# YOTSUBA_AP_EM_ver_1_0.net
KiCad netlist of a schematic drawn in EAGLE
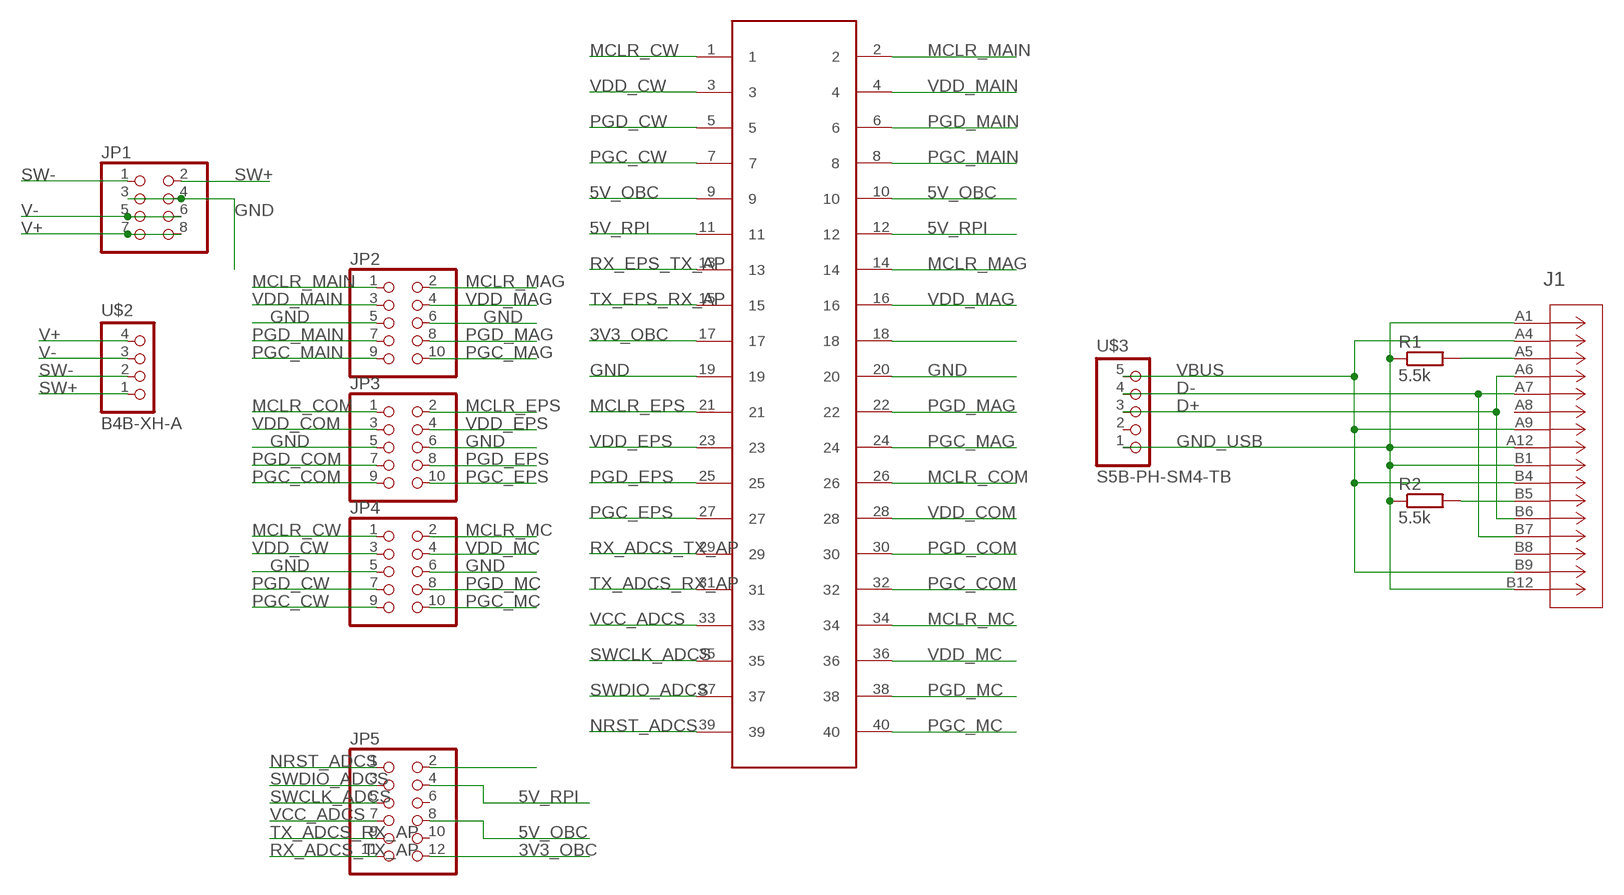
[diagram p0: schematic, sheet 1]

(export (version "E")
  (design (tool "Eeschema 10.0.6"))
  (components
    (comp (ref "J1")
      (value "217182-0001")
      (footprint "eagle-import:CONN_217182-0001_MOL")
      (fields (field (name "COPYRIGHT") "Copyright (C) 2022 Ultra Librarian. All rights reserved."))
      (libsource (lib "eagle-import") (part "217182-0001"))
    )
    (comp (ref "JP1")
      (value "PINHD-2X4")
      (footprint "eagle-import:2X04")
      (libsource (lib "eagle-import") (part "PINHD-2X4"))
    )
    (comp (ref "JP2")
      (value "PINHD-2X5")
      (footprint "eagle-import:2X05")
      (libsource (lib "eagle-import") (part "PINHD-2X5"))
    )
    (comp (ref "JP3")
      (value "PINHD-2X5")
      (footprint "eagle-import:2X05")
      (libsource (lib "eagle-import") (part "PINHD-2X5"))
    )
    (comp (ref "JP4")
      (value "PINHD-2X5")
      (footprint "eagle-import:2X05")
      (libsource (lib "eagle-import") (part "PINHD-2X5"))
    )
    (comp (ref "JP5")
      (value "PINHD-2X6")
      (footprint "eagle-import:2X06")
      (libsource (lib "eagle-import") (part "PINHD-2X6"))
    )
    (comp (ref "R1")
      (value "5.5k")
      (footprint "eagle-import:M2012")
      (libsource (lib "eagle-import") (part "R-EU_M2012"))
    )
    (comp (ref "R2")
      (value "5.5k")
      (footprint "eagle-import:M2012")
      (libsource (lib "eagle-import") (part "R-EU_M2012"))
    )
    (comp (ref "U$1")
      (value "M50-3902042")
      (footprint "eagle-import:M50-3902042")
      (libsource (lib "eagle-import") (part "M50-3902042"))
    )
    (comp (ref "U$2")
      (value "B4B-XH-A")
      (footprint "eagle-import:B4B-XH-A")
      (libsource (lib "eagle-import") (part "B4B-XH-A"))
    )
    (comp (ref "U$3")
      (value "S5B-PH-SM4-TB")
      (footprint "eagle-import:S5B-PH-SM4-TB")
      (libsource (lib "eagle-import") (part "S5B-PH-SM4-TB"))
    )
  )
  (nets
    (net (code "1") (name "/3V3_OBC") (class "Default")
      (node (ref "JP5") (pin "12") (pinfunction "12_12") (pintype "passive"))
      (node (ref "U$1") (pin "17") (pinfunction "17_17") (pintype "bidirectional"))
    )
    (net (code "2") (name "/5V_OBC") (class "Default")
      (node (ref "JP5") (pin "8") (pinfunction "8_8") (pintype "passive"))
      (node (ref "U$1") (pin "10") (pinfunction "10_10") (pintype "bidirectional"))
      (node (ref "U$1") (pin "9") (pinfunction "9_9") (pintype "bidirectional"))
    )
    (net (code "3") (name "/5V_RPI") (class "Default")
      (node (ref "JP5") (pin "4") (pinfunction "4_4") (pintype "passive"))
      (node (ref "U$1") (pin "11") (pinfunction "11_11") (pintype "bidirectional"))
      (node (ref "U$1") (pin "12") (pinfunction "12_12") (pintype "bidirectional"))
    )
    (net (code "4") (name "/D+") (class "Default")
      (node (ref "J1") (pin "A6") (pinfunction "DP1_A6") (pintype "bidirectional"))
      (node (ref "J1") (pin "B6") (pinfunction "DP2_B6") (pintype "bidirectional"))
      (node (ref "U$3") (pin "3") (pinfunction "3_3") (pintype "passive"))
    )
    (net (code "5") (name "/D-") (class "Default")
      (node (ref "J1") (pin "A7") (pinfunction "DN1_A7") (pintype "bidirectional"))
      (node (ref "J1") (pin "B7") (pinfunction "DN2_B7") (pintype "bidirectional"))
      (node (ref "U$3") (pin "4") (pinfunction "4_4") (pintype "passive"))
    )
    (net (code "6") (name "/GND") (class "Default")
      (node (ref "JP1") (pin "3") (pinfunction "3_3") (pintype "passive"))
      (node (ref "JP1") (pin "4") (pinfunction "4_4") (pintype "passive"))
      (node (ref "JP2") (pin "5") (pinfunction "5_5") (pintype "passive"))
      (node (ref "JP2") (pin "6") (pinfunction "6_6") (pintype "passive"))
      (node (ref "JP3") (pin "5") (pinfunction "5_5") (pintype "passive"))
      (node (ref "JP3") (pin "6") (pinfunction "6_6") (pintype "passive"))
      (node (ref "JP4") (pin "5") (pinfunction "5_5") (pintype "passive"))
      (node (ref "JP4") (pin "6") (pinfunction "6_6") (pintype "passive"))
      (node (ref "U$1") (pin "19") (pinfunction "19_19") (pintype "bidirectional"))
      (node (ref "U$1") (pin "20") (pinfunction "20_20") (pintype "bidirectional"))
    )
    (net (code "7") (name "/GND_USB") (class "Default")
      (node (ref "J1") (pin "A1") (pinfunction "GND_2_A1") (pintype "passive"))
      (node (ref "J1") (pin "A12") (pinfunction "GND_3_A12") (pintype "passive"))
      (node (ref "J1") (pin "B1") (pinfunction "GND_4_B1") (pintype "passive"))
      (node (ref "J1") (pin "B12") (pinfunction "GND_B12") (pintype "passive"))
      (node (ref "R1") (pin "1") (pinfunction "1_1") (pintype "passive"))
      (node (ref "R2") (pin "1") (pinfunction "1_1") (pintype "passive"))
      (node (ref "U$3") (pin "1") (pinfunction "1_1") (pintype "passive"))
    )
    (net (code "8") (name "/MCLR_COM") (class "Default")
      (node (ref "JP3") (pin "1") (pinfunction "1_1") (pintype "passive"))
      (node (ref "U$1") (pin "26") (pinfunction "26_26") (pintype "bidirectional"))
    )
    (net (code "9") (name "/MCLR_CW") (class "Default")
      (node (ref "JP4") (pin "1") (pinfunction "1_1") (pintype "passive"))
      (node (ref "U$1") (pin "1") (pinfunction "1_1") (pintype "bidirectional"))
    )
    (net (code "10") (name "/MCLR_EPS") (class "Default")
      (node (ref "JP3") (pin "2") (pinfunction "2_2") (pintype "passive"))
      (node (ref "U$1") (pin "21") (pinfunction "21_21") (pintype "bidirectional"))
    )
    (net (code "11") (name "/MCLR_MAG") (class "Default")
      (node (ref "JP2") (pin "2") (pinfunction "2_2") (pintype "passive"))
      (node (ref "U$1") (pin "14") (pinfunction "14_14") (pintype "bidirectional"))
    )
    (net (code "12") (name "/MCLR_MAIN") (class "Default")
      (node (ref "JP2") (pin "1") (pinfunction "1_1") (pintype "passive"))
      (node (ref "U$1") (pin "2") (pinfunction "2_2") (pintype "bidirectional"))
    )
    (net (code "13") (name "/MCLR_MC") (class "Default")
      (node (ref "JP4") (pin "2") (pinfunction "2_2") (pintype "passive"))
      (node (ref "U$1") (pin "34") (pinfunction "34_34") (pintype "bidirectional"))
    )
    (net (code "14") (name "/NRST_ADCS") (class "Default")
      (node (ref "JP5") (pin "1") (pinfunction "1_1") (pintype "passive"))
      (node (ref "U$1") (pin "39") (pinfunction "39_39") (pintype "bidirectional"))
    )
    (net (code "15") (name "/PGC_COM") (class "Default")
      (node (ref "JP3") (pin "9") (pinfunction "9_9") (pintype "passive"))
      (node (ref "U$1") (pin "32") (pinfunction "32_32") (pintype "bidirectional"))
    )
    (net (code "16") (name "/PGC_CW") (class "Default")
      (node (ref "JP4") (pin "9") (pinfunction "9_9") (pintype "passive"))
      (node (ref "U$1") (pin "7") (pinfunction "7_7") (pintype "bidirectional"))
    )
    (net (code "17") (name "/PGC_EPS") (class "Default")
      (node (ref "JP3") (pin "10") (pinfunction "10_10") (pintype "passive"))
      (node (ref "U$1") (pin "27") (pinfunction "27_27") (pintype "bidirectional"))
    )
    (net (code "18") (name "/PGC_MAG") (class "Default")
      (node (ref "JP2") (pin "10") (pinfunction "10_10") (pintype "passive"))
      (node (ref "U$1") (pin "24") (pinfunction "24_24") (pintype "bidirectional"))
    )
    (net (code "19") (name "/PGC_MAIN") (class "Default")
      (node (ref "JP2") (pin "9") (pinfunction "9_9") (pintype "passive"))
      (node (ref "U$1") (pin "8") (pinfunction "8_8") (pintype "bidirectional"))
    )
    (net (code "20") (name "/PGC_MC") (class "Default")
      (node (ref "JP4") (pin "10") (pinfunction "10_10") (pintype "passive"))
      (node (ref "U$1") (pin "40") (pinfunction "40_40") (pintype "bidirectional"))
    )
    (net (code "21") (name "/PGD_COM") (class "Default")
      (node (ref "JP3") (pin "7") (pinfunction "7_7") (pintype "passive"))
      (node (ref "U$1") (pin "30") (pinfunction "30_30") (pintype "bidirectional"))
    )
    (net (code "22") (name "/PGD_CW") (class "Default")
      (node (ref "JP4") (pin "7") (pinfunction "7_7") (pintype "passive"))
      (node (ref "U$1") (pin "5") (pinfunction "5_5") (pintype "bidirectional"))
    )
    (net (code "23") (name "/PGD_EPS") (class "Default")
      (node (ref "JP3") (pin "8") (pinfunction "8_8") (pintype "passive"))
      (node (ref "U$1") (pin "25") (pinfunction "25_25") (pintype "bidirectional"))
    )
    (net (code "24") (name "/PGD_MAG") (class "Default")
      (node (ref "JP2") (pin "8") (pinfunction "8_8") (pintype "passive"))
      (node (ref "U$1") (pin "22") (pinfunction "22_22") (pintype "bidirectional"))
    )
    (net (code "25") (name "/PGD_MAIN") (class "Default")
      (node (ref "JP2") (pin "7") (pinfunction "7_7") (pintype "passive"))
      (node (ref "U$1") (pin "6") (pinfunction "6_6") (pintype "bidirectional"))
    )
    (net (code "26") (name "/PGD_MC") (class "Default")
      (node (ref "JP4") (pin "8") (pinfunction "8_8") (pintype "passive"))
      (node (ref "U$1") (pin "38") (pinfunction "38_38") (pintype "bidirectional"))
    )
    (net (code "27") (name "/RX_ADCS_TX_AP") (class "Default")
      (node (ref "JP5") (pin "11") (pinfunction "11_11") (pintype "passive"))
      (node (ref "U$1") (pin "29") (pinfunction "29_29") (pintype "bidirectional"))
    )
    (net (code "28") (name "/RX_EPS_TX_AP") (class "Default")
      (node (ref "U$1") (pin "13") (pinfunction "13_13") (pintype "bidirectional"))
    )
    (net (code "29") (name "/SW+") (class "Default")
      (node (ref "JP1") (pin "2") (pinfunction "2_2") (pintype "passive"))
      (node (ref "U$2") (pin "1") (pinfunction "1_1") (pintype "passive"))
    )
    (net (code "30") (name "/SW-") (class "Default")
      (node (ref "JP1") (pin "1") (pinfunction "1_1") (pintype "passive"))
      (node (ref "U$2") (pin "2") (pinfunction "2_2") (pintype "passive"))
    )
    (net (code "31") (name "/SWCLK_ADCS") (class "Default")
      (node (ref "JP5") (pin "5") (pinfunction "5_5") (pintype "passive"))
      (node (ref "U$1") (pin "35") (pinfunction "35_35") (pintype "bidirectional"))
    )
    (net (code "32") (name "/SWDIO_ADCS") (class "Default")
      (node (ref "JP5") (pin "3") (pinfunction "3_3") (pintype "passive"))
      (node (ref "U$1") (pin "37") (pinfunction "37_37") (pintype "bidirectional"))
    )
    (net (code "33") (name "/TX_ADCS_RX_AP") (class "Default")
      (node (ref "JP5") (pin "9") (pinfunction "9_9") (pintype "passive"))
      (node (ref "U$1") (pin "31") (pinfunction "31_31") (pintype "bidirectional"))
    )
    (net (code "34") (name "/TX_EPS_RX_AP") (class "Default")
      (node (ref "U$1") (pin "15") (pinfunction "15_15") (pintype "bidirectional"))
    )
    (net (code "35") (name "/V+") (class "Default")
      (node (ref "JP1") (pin "7") (pinfunction "7_7") (pintype "passive"))
      (node (ref "JP1") (pin "8") (pinfunction "8_8") (pintype "passive"))
      (node (ref "U$2") (pin "4") (pinfunction "4_4") (pintype "passive"))
    )
    (net (code "36") (name "/V-") (class "Default")
      (node (ref "JP1") (pin "5") (pinfunction "5_5") (pintype "passive"))
      (node (ref "JP1") (pin "6") (pinfunction "6_6") (pintype "passive"))
      (node (ref "U$2") (pin "3") (pinfunction "3_3") (pintype "passive"))
    )
    (net (code "37") (name "/VBUS") (class "Default")
      (node (ref "J1") (pin "A4") (pinfunction "VBUS_2_A4") (pintype "passive"))
      (node (ref "J1") (pin "A9") (pinfunction "VBUS_3_A9") (pintype "passive"))
      (node (ref "J1") (pin "B4") (pinfunction "VBUS_4_B4") (pintype "passive"))
      (node (ref "J1") (pin "B9") (pinfunction "VBUS_B9") (pintype "passive"))
      (node (ref "U$3") (pin "5") (pinfunction "5_5") (pintype "passive"))
    )
    (net (code "38") (name "/VCC_ADCS") (class "Default")
      (node (ref "JP5") (pin "7") (pinfunction "7_7") (pintype "passive"))
      (node (ref "U$1") (pin "33") (pinfunction "33_33") (pintype "bidirectional"))
    )
    (net (code "39") (name "/VDD_COM") (class "Default")
      (node (ref "JP3") (pin "3") (pinfunction "3_3") (pintype "passive"))
      (node (ref "U$1") (pin "28") (pinfunction "28_28") (pintype "bidirectional"))
    )
    (net (code "40") (name "/VDD_CW") (class "Default")
      (node (ref "JP4") (pin "3") (pinfunction "3_3") (pintype "passive"))
      (node (ref "U$1") (pin "3") (pinfunction "3_3") (pintype "bidirectional"))
    )
    (net (code "41") (name "/VDD_EPS") (class "Default")
      (node (ref "JP3") (pin "4") (pinfunction "4_4") (pintype "passive"))
      (node (ref "U$1") (pin "23") (pinfunction "23_23") (pintype "bidirectional"))
    )
    (net (code "42") (name "/VDD_MAG") (class "Default")
      (node (ref "JP2") (pin "4") (pinfunction "4_4") (pintype "passive"))
      (node (ref "U$1") (pin "16") (pinfunction "16_16") (pintype "bidirectional"))
    )
    (net (code "43") (name "/VDD_MAIN") (class "Default")
      (node (ref "JP2") (pin "3") (pinfunction "3_3") (pintype "passive"))
      (node (ref "U$1") (pin "4") (pinfunction "4_4") (pintype "bidirectional"))
    )
    (net (code "44") (name "/VDD_MC") (class "Default")
      (node (ref "JP4") (pin "4") (pinfunction "4_4") (pintype "passive"))
      (node (ref "U$1") (pin "36") (pinfunction "36_36") (pintype "bidirectional"))
    )
    (net (code "45") (name "Net-(J1-CC1)") (class "Default")
      (node (ref "J1") (pin "A5") (pinfunction "CC1_A5") (pintype "bidirectional"))
      (node (ref "R1") (pin "2") (pinfunction "2_2") (pintype "passive"))
    )
    (net (code "46") (name "Net-(J1-CC2)") (class "Default")
      (node (ref "J1") (pin "B5") (pinfunction "CC2_B5") (pintype "bidirectional"))
      (node (ref "R2") (pin "2") (pinfunction "2_2") (pintype "passive"))
    )
    (net (code "47") (name "unconnected-(J1-SBU1-PadA8)") (class "Default")
      (node (ref "J1") (pin "A8") (pinfunction "SBU1_A8") (pintype "bidirectional"))
    )
    (net (code "48") (name "unconnected-(J1-SBU2-PadB8)") (class "Default")
      (node (ref "J1") (pin "B8") (pinfunction "SBU2_B8") (pintype "bidirectional"))
    )
    (net (code "49") (name "unconnected-(JP5-Pad2)") (class "Default")
      (node (ref "JP5") (pin "2") (pinfunction "2_2") (pintype "passive"))
    )
    (net (code "50") (name "unconnected-(JP5-Pad6)") (class "Default")
      (node (ref "JP5") (pin "6") (pinfunction "6_6") (pintype "passive"))
    )
    (net (code "51") (name "unconnected-(JP5-Pad10)") (class "Default")
      (node (ref "JP5") (pin "10") (pinfunction "10_10") (pintype "passive"))
    )
    (net (code "52") (name "unconnected-(U$1-Pad18)") (class "Default")
      (node (ref "U$1") (pin "18") (pinfunction "18_18") (pintype "bidirectional"))
    )
    (net (code "53") (name "unconnected-(U$3-Pad2)") (class "Default")
      (node (ref "U$3") (pin "2") (pinfunction "2_2") (pintype "passive"))
    )
  )
)
